# PowerManagement.net
KiCad netlist of a schematic drawn in Altium Designer
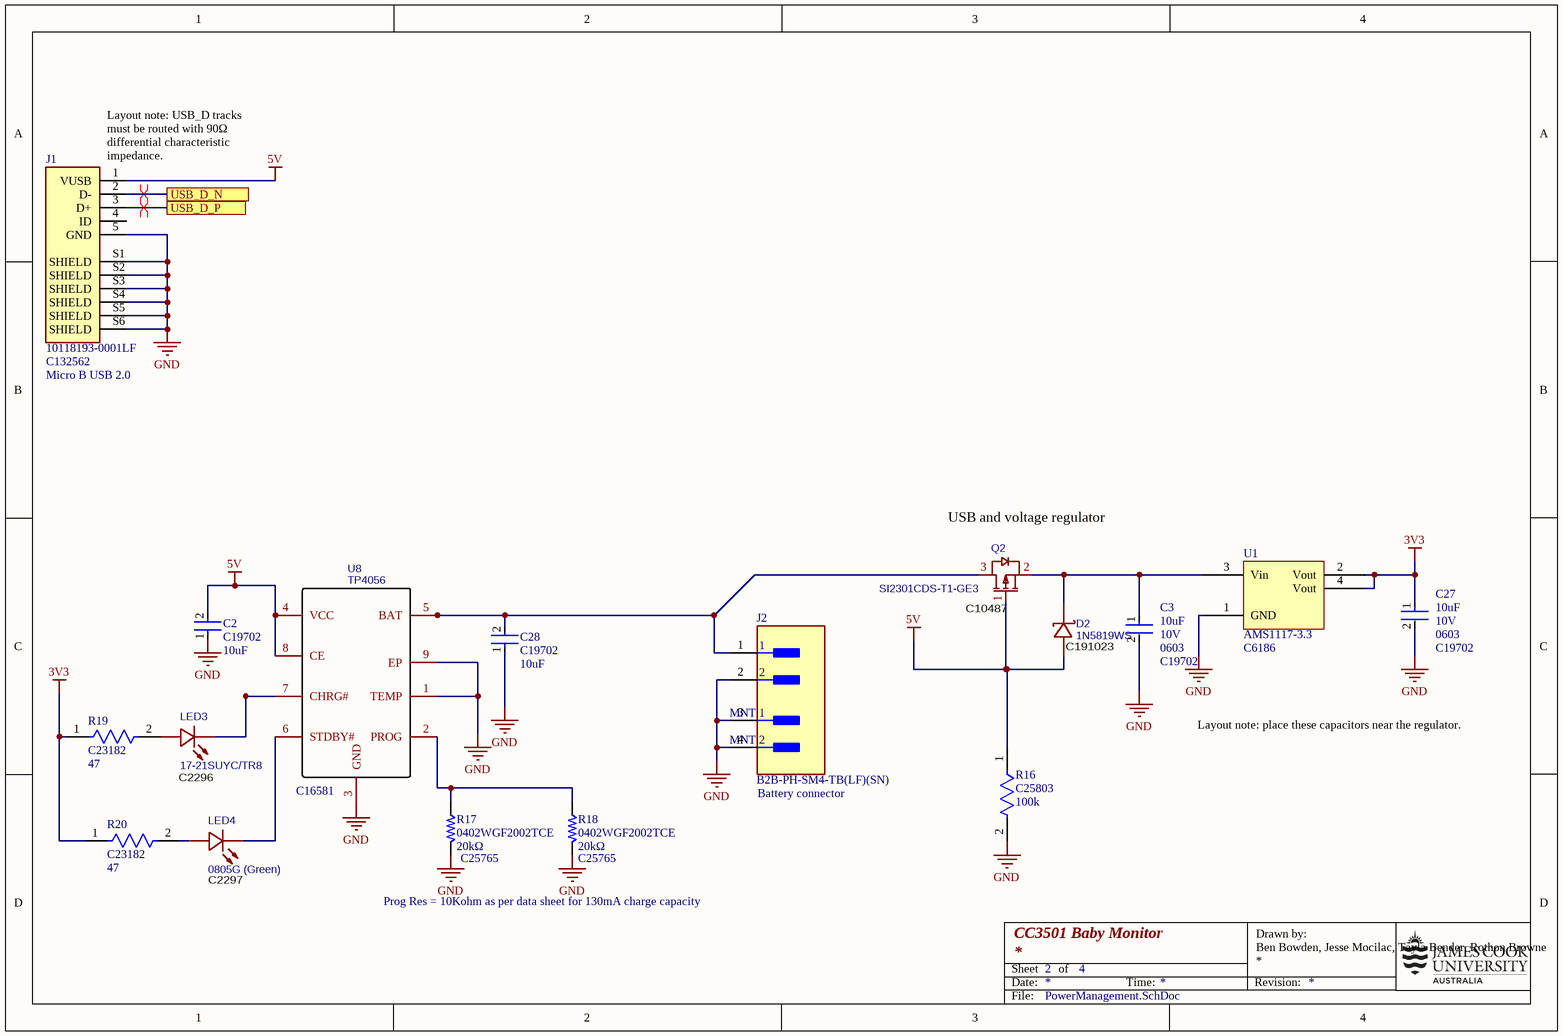
[diagram p0: PowerManagement.SchDoc]

(export (version "E")
  (design (tool "Eeschema 10.0.6"))
  (components
    (comp (ref "C2")
      (value "CL10A106KP8NNNC")
      (footprint "FP-CL10-IPC_B")
      (description "Cap Ceramic 10uF 10V X5R ±10% Pad SMD 0603 +85°C T/R")
      (fields
        (field (name "JLCPCB PART") "C19702")
        (field (name "CAPACITANCE") "10uF")
        (field (name "TOLERANCE") "10%")
      )
      (libsource (lib "James Cook University") (part "b4654b650e69147ec39a6b967a45e02"))
    )
    (comp (ref "C3")
      (value "CL10A106KP8NNNC")
      (footprint "FP-CL10-IPC_B")
      (description "Cap Ceramic 10uF 10V X5R ±10% Pad SMD 0603 +85°C T/R")
      (fields
        (field (name "TOLERANCE") "10%")
        (field (name "VOLTAGE RATING") "10V")
        (field (name "CASE CODE (IMPERIAL)") "0603")
        (field (name "JLCPCB PART") "C19702")
        (field (name "CAPACITANCE") "10uF")
      )
      (libsource (lib "James Cook University") (part "b4654b650e69147ec39a6b967a45e02"))
    )
    (comp (ref "C27")
      (value "CL10A106KP8NNNC")
      (footprint "FP-CL10-IPC_B")
      (description "Cap Ceramic 10uF 10V X5R ±10% Pad SMD 0603 +85°C T/R")
      (fields
        (field (name "TOLERANCE") "10%")
        (field (name "VOLTAGE RATING") "10V")
        (field (name "CASE CODE (IMPERIAL)") "0603")
        (field (name "JLCPCB PART") "C19702")
        (field (name "CAPACITANCE") "10uF")
      )
      (libsource (lib "James Cook University") (part "b4654b650e69147ec39a6b967a45e02"))
    )
    (comp (ref "C28")
      (value "CL10A106KP8NNNC")
      (footprint "FP-CL10-IPC_B")
      (description "Cap Ceramic 10uF 10V X5R ±10% Pad SMD 0603 +85°C T/R")
      (fields
        (field (name "JLCPCB PART") "C19702")
        (field (name "CAPACITANCE") "10uF")
        (field (name "TOLERANCE") "10%")
      )
      (libsource (lib "James Cook University") (part "b4654b650e69147ec39a6b967a45e02"))
    )
    (comp (ref "D2")
      (value "1N5819WS")
      (footprint "SOD-323_L1.8-W1.3-LS2.5-RD")
      (fields
        (field (name "SUPPLIER PART") "C191023")
        (field (name "MANUFACTURER") "Hottech(合科泰)")
        (field (name "CONTRIBUTOR") "LCSC")
      )
      (libsource (lib "altium-import") (part "root_3_1N5819WS_"))
    )
    (comp (ref "J1")
      (value "10118193-0001LF")
      (footprint "FCI_10118193-0001LF")
      (description "USB - micro B USB 2.0 Receptacle Connector 5 Position Surface Mount, Right Angle; Through Hole")
      (fields (field (name "MF") "Amphenol ICC") (field (name "JLCPCB PART") "C132562"))
      (libsource (lib "James Cook University") (part "10118193-0001LF"))
    )
    (comp (ref "J2")
      (value "B2B-PH-SM4-TB(LF)(SN)")
      (footprint "FP-B2B-PH-SM4-TB_LF_SN-MFG")
      (description "CONN HEADER SMD 2POS 2MM")
      (libsource (lib "Altium Content Vault") (part "56ec3178a87b3978bdc1b3682cd516a"))
    )
    (comp (ref "LED3")
      (value "17-21SUYC/TR8")
      (footprint "LED0805-R-RD")
      (fields
        (field (name "MANUFACTURER") "KENTO")
        (field (name "MANUFACTURER PART") "KT-0805黄灯")
        (field (name "SUPPLIER PART") "C2296")
      )
      (libsource (lib "altium-import") (part "root_2_17-21SUYC/TR8_"))
    )
    (comp (ref "LED4")
      (value "0805G (Green)")
      (footprint "LED0805-R-RD")
      (fields
        (field (name "MANUFACTURER") "KENTO")
        (field (name "MANUFACTURER PART") "KT-0805G")
        (field (name "SUPPLIER PART") "C2297")
      )
      (libsource (lib "altium-import") (part "root_2_0805G (Green)_"))
    )
    (comp (ref "Q2")
      (value "SI2301CDS-T1-GE3")
      (footprint "SOT-23-3_L3.0-W1.7-P0.95-LS2.9-BR")
      (fields (field (name "MANUFACTURER") "VISHAY(威世)") (field (name "SUPPLIER PART") "C10487"))
      (libsource (lib "altium-import") (part "root_1_SI2301CDS-T1-GE3_"))
    )
    (comp (ref "R16")
      (value "0603WAF1003T5E")
      (footprint "FP-CRCW0603-e3-IPC_B")
      (description "RES Thick Film, 100kΩ, 1%, 0.1W, 100ppm/°C, 0603")
      (fields
        (field (name "JLCPCB PART") "C25803")
        (field (name "RESISTANCE") "100k")
        (field (name "TOLERANCE") "1%")
      )
      (libsource (lib "James Cook University") (part "1029c3af85768c4190bb7ad29bc67b5"))
    )
    (comp (ref "R17")
      (value "0402WGF2002TCE")
      (footprint "RES-0402")
      (description "Resistor, 20kΩ, ±1%, 62.5mW, 50V, ±100ppm/℃, -55℃~+155℃, SMD 0402")
      (fields
        (field (name "RESISTANCE") "20kΩ")
        (field (name "TOLERANCE") "±1%")
        (field (name "JLCPCB BASIC PART") "Yes")
        (field (name "JLCPCB PART NUMBER") "C25765")
      )
      (libsource (lib "James Cook University") (part "1206W4F7500T5E"))
    )
    (comp (ref "R18")
      (value "0402WGF2002TCE")
      (footprint "RES-0402")
      (description "Resistor, 20kΩ, ±1%, 62.5mW, 50V, ±100ppm/℃, -55℃~+155℃, SMD 0402")
      (fields
        (field (name "RESISTANCE") "20kΩ")
        (field (name "TOLERANCE") "±1%")
        (field (name "JLCPCB BASIC PART") "Yes")
        (field (name "JLCPCB PART NUMBER") "C25765")
      )
      (libsource (lib "James Cook University") (part "1206W4F7500T5E"))
    )
    (comp (ref "R19")
      (value "0603WAF1003T5E")
      (footprint "FP-CRCW0603-e3-IPC_B")
      (description "RES Thick Film, 47Ω, 1%, 0.1W, 100ppm/°C, 0603")
      (fields
        (field (name "JLCPCB PART") "C23182")
        (field (name "RESISTANCE") "47")
        (field (name "TOLERANCE") "1%")
      )
      (libsource (lib "James Cook University") (part "1029c3af85768c4190bb7ad29bc67b5"))
    )
    (comp (ref "R20")
      (value "0603WAF1003T5E")
      (footprint "FP-CRCW0603-e3-IPC_B")
      (description "RES Thick Film, 47Ω, 1%, 0.1W, 100ppm/°C, 0603")
      (fields
        (field (name "JLCPCB PART") "C23182")
        (field (name "RESISTANCE") "47")
        (field (name "TOLERANCE") "1%")
      )
      (libsource (lib "James Cook University") (part "1029c3af85768c4190bb7ad29bc67b5"))
    )
    (comp (ref "U1")
      (value "AMS1117-3.3")
      (footprint "SOT230P700X180-4N")
      (description "3.3V 1A LOW DROPOUT VOLTAGE REGULATOR SOT-223")
      (fields (field (name "JLCPCB PART") "C6186"))
      (libsource (lib "James Cook University") (part "AMS1117-3.3"))
    )
    (comp (ref "U8")
      (value "TP4056")
      (footprint "ESOP-8_L4.9-W3.9-P1.27-LS6.0-BL-EP")
      (fields
        (field (name "MANUFACTURER") "TOPPOWER(南京拓微)")
        (field (name "MANUFACTURER PART") "TP4056-42-ESOP8")
        (field (name "JLCPCB PART") "C16581")
        (field (name "CONTRIBUTOR") "Guest")
      )
      (libsource (lib "altium-import") (part "root_0_TP4056_"))
    )
  )
  (nets
    (net (code "1") (name "/USB_D_N") (class "Default")
      (node (ref "J1") (pin "2") (pinfunction "D-_2") (pintype "passive"))
    )
    (net (code "2") (name "/USB_D_P") (class "Default")
      (node (ref "J1") (pin "3") (pinfunction "D+_3") (pintype "passive"))
    )
    (net (code "3") (name "3V3") (class "Default")
      (node (ref "C27") (pin "1") (pinfunction "1_1") (pintype "passive"))
      (node (ref "R19") (pin "1") (pinfunction "1_1") (pintype "passive"))
      (node (ref "R20") (pin "1") (pinfunction "1_1") (pintype "passive"))
      (node (ref "U1") (pin "2") (pinfunction "Vout_2") (pintype "power_in"))
      (node (ref "U1") (pin "4") (pinfunction "Vout_4") (pintype "power_in"))
    )
    (net (code "4") (name "5V") (class "Default")
      (node (ref "C2") (pin "2") (pinfunction "2_2") (pintype "passive"))
      (node (ref "D2") (pin "2") (pinfunction "A_2") (pintype "passive"))
      (node (ref "J1") (pin "1") (pinfunction "VUSB_1") (pintype "passive"))
      (node (ref "Q2") (pin "1") (pinfunction "G_1") (pintype "passive"))
      (node (ref "R16") (pin "1") (pinfunction "1_1") (pintype "passive"))
      (node (ref "U8") (pin "4") (pinfunction "VCC_4") (pintype "passive"))
      (node (ref "U8") (pin "8") (pinfunction "CE_8") (pintype "passive"))
    )
    (net (code "5") (name "GND") (class "Default")
      (node (ref "C2") (pin "1") (pinfunction "1_1") (pintype "passive"))
      (node (ref "C27") (pin "2") (pinfunction "2_2") (pintype "passive"))
      (node (ref "C28") (pin "1") (pinfunction "1_1") (pintype "passive"))
      (node (ref "C3") (pin "2") (pinfunction "2_2") (pintype "passive"))
      (node (ref "J1") (pin "5") (pinfunction "GND_5") (pintype "passive"))
      (node (ref "J1") (pin "S1") (pinfunction "SHIELD_S1") (pintype "passive"))
      (node (ref "J1") (pin "S2") (pinfunction "SHIELD_S2") (pintype "passive"))
      (node (ref "J1") (pin "S3") (pinfunction "SHIELD_S3") (pintype "passive"))
      (node (ref "J1") (pin "S4") (pinfunction "SHIELD_S4") (pintype "passive"))
      (node (ref "J1") (pin "S5") (pinfunction "SHIELD_S5") (pintype "passive"))
      (node (ref "J1") (pin "S6") (pinfunction "SHIELD_S6") (pintype "passive"))
      (node (ref "J2") (pin "2") (pinfunction "2_2") (pintype "passive"))
      (node (ref "J2") (pin "3") (pinfunction "MNT_1_3") (pintype "passive"))
      (node (ref "J2") (pin "4") (pinfunction "MNT_2_4") (pintype "passive"))
      (node (ref "R16") (pin "2") (pinfunction "2_2") (pintype "passive"))
      (node (ref "R17") (pin "2") (pinfunction "2_2") (pintype "passive"))
      (node (ref "R18") (pin "2") (pinfunction "2_2") (pintype "passive"))
      (node (ref "U1") (pin "1") (pinfunction "GND_1") (pintype "power_in"))
      (node (ref "U8") (pin "1") (pinfunction "TEMP_1") (pintype "passive"))
      (node (ref "U8") (pin "3") (pinfunction "GND_3") (pintype "passive"))
      (node (ref "U8") (pin "9") (pinfunction "EP_9") (pintype "passive"))
    )
    (net (code "6") (name "Net-(D2-K)") (class "Default")
      (node (ref "C3") (pin "1") (pinfunction "1_1") (pintype "passive"))
      (node (ref "D2") (pin "1") (pinfunction "K_1") (pintype "passive"))
      (node (ref "Q2") (pin "2") (pinfunction "S_2") (pintype "passive"))
      (node (ref "U1") (pin "3") (pinfunction "Vin_3") (pintype "power_in"))
    )
    (net (code "7") (name "Net-(LED3-+)") (class "Default")
      (node (ref "LED3") (pin "1") (pinfunction "+_1") (pintype "passive"))
      (node (ref "R19") (pin "2") (pinfunction "2_2") (pintype "passive"))
    )
    (net (code "8") (name "Net-(LED3--)") (class "Default")
      (node (ref "LED3") (pin "2") (pinfunction "-_2") (pintype "passive"))
      (node (ref "U8") (pin "7") (pinfunction "CHRG#_7") (pintype "passive"))
    )
    (net (code "9") (name "Net-(LED4-A)") (class "Default")
      (node (ref "LED4") (pin "1") (pinfunction "A_1") (pintype "passive"))
      (node (ref "R20") (pin "2") (pinfunction "2_2") (pintype "passive"))
    )
    (net (code "10") (name "Net-(LED4-K)") (class "Default")
      (node (ref "LED4") (pin "2") (pinfunction "K_2") (pintype "passive"))
      (node (ref "U8") (pin "6") (pinfunction "STDBY#_6") (pintype "passive"))
    )
    (net (code "11") (name "Net-(Q2-D)") (class "Default")
      (node (ref "C28") (pin "2") (pinfunction "2_2") (pintype "passive"))
      (node (ref "J2") (pin "1") (pinfunction "1_1") (pintype "passive"))
      (node (ref "Q2") (pin "3") (pinfunction "D_3") (pintype "passive"))
      (node (ref "U8") (pin "5") (pinfunction "BAT_5") (pintype "passive"))
    )
    (net (code "12") (name "Net-(U8-PROG)") (class "Default")
      (node (ref "R17") (pin "1") (pinfunction "1_1") (pintype "passive"))
      (node (ref "R18") (pin "1") (pinfunction "1_1") (pintype "passive"))
      (node (ref "U8") (pin "2") (pinfunction "PROG_2") (pintype "passive"))
    )
    (net (code "13") (name "unconnected-(J1-ID-Pad4)") (class "Default")
      (node (ref "J1") (pin "4") (pinfunction "ID_4") (pintype "passive"))
    )
  )
)
